# Pigeon.net
KiCad netlist of a schematic drawn in Altium Designer
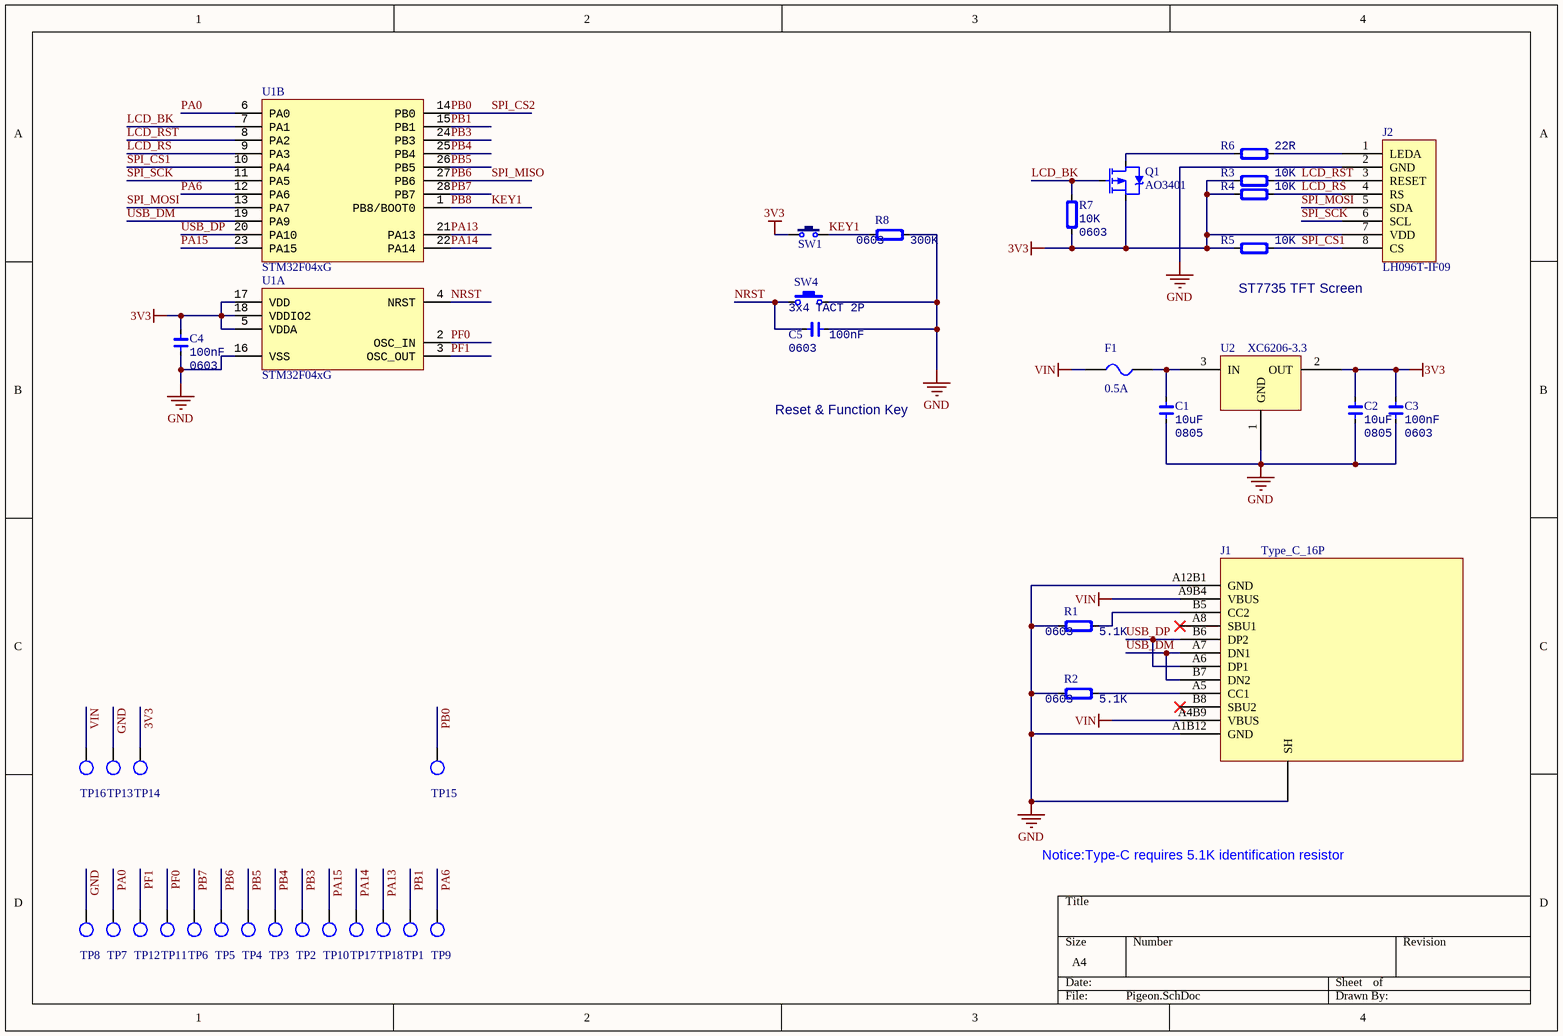
[diagram p0: Pigeon.SchDoc]

(export (version "E")
  (design (tool "Eeschema 10.0.6"))
  (components
    (comp (ref "C1")
      (value "10uF")
      (footprint "PCB_PassiveCap:CAP_0805")
      (description "Capacitor")
      (fields (field (name "TYPE") "0805") (field (name "Comment") "C0805"))
      (libsource (lib "SCH_Passive") (part "Cap_0805"))
    )
    (comp (ref "C2")
      (value "10uF")
      (footprint "PCB_PassiveCap:CAP_0805")
      (description "Capacitor")
      (fields (field (name "TYPE") "0805") (field (name "Comment") "C0805"))
      (libsource (lib "SCH_Passive") (part "Cap_0805"))
    )
    (comp (ref "C3")
      (value "100nF")
      (footprint "PCB_PassiveCap:CAP_0603")
      (description "Capacitor")
      (fields (field (name "TYPE") "0603") (field (name "Comment") "C0603"))
      (libsource (lib "SCH_Passive") (part "Cap_0603"))
    )
    (comp (ref "C4")
      (value "100nF")
      (footprint "PCB_PassiveCap:CAP_0603")
      (description "Capacitor")
      (fields (field (name "TYPE") "0603") (field (name "Comment") "C0603"))
      (libsource (lib "SCH_Passive") (part "Cap_0603"))
    )
    (comp (ref "C5")
      (value "100nF")
      (footprint "PCB_PassiveCap:CAP_0603")
      (description "Capacitor")
      (fields (field (name "TYPE") "0603") (field (name "Comment") "C0603"))
      (libsource (lib "") (part "Cap_0603_1"))
    )
    (comp (ref "F1")
      (value "0.5A")
      (footprint "FU 0805")
      (description "自恢复 0.5A C75464")
      (fields (field (name "版权归属") "源创客"))
      (libsource (lib "10.1 - 保险丝-晶振") (part "FU"))
    )
    (comp (ref "J1")
      (value "Type_C_16P")
      (footprint "Type_C_16P")
      (libsource (lib "LuLib") (part "Type_C_16P"))
    )
    (comp (ref "J2")
      (value "LH096T-IF09")
      (footprint "LH096T-IF09")
      (libsource (lib "LuLib") (part "LH096T-IF09"))
    )
    (comp (ref "Q1") (value "AO3401") (footprint "SOT23-3") (libsource (lib "Schlib1") (part "AO3401")))
    (comp (ref "R1")
      (value "5.1K")
      (footprint "PCB_PassiveRes:RES_0603")
      (description "Resistor 5%")
      (fields (field (name "TYPE") "0603") (field (name "Comment") "R0603"))
      (libsource (lib "SCH_Passive") (part "Res_0603"))
    )
    (comp (ref "R2")
      (value "5.1K")
      (footprint "PCB_PassiveRes:RES_0603")
      (description "Resistor 5%")
      (fields (field (name "TYPE") "0603") (field (name "Comment") "R0603"))
      (libsource (lib "SCH_Passive") (part "Res_0603"))
    )
    (comp (ref "R3")
      (value "10K")
      (footprint "PCB_PassiveRes:RES_0603")
      (description "Resistor")
      (fields (field (name "Comment") "R0603"))
      (libsource (lib "SCH_Passive") (part "Res_0603"))
    )
    (comp (ref "R4")
      (value "10K")
      (footprint "PCB_PassiveRes:RES_0603")
      (description "Resistor")
      (fields (field (name "Comment") "R0603"))
      (libsource (lib "SCH_Passive") (part "Res_0603"))
    )
    (comp (ref "R5")
      (value "10K")
      (footprint "PCB_PassiveRes:RES_0603")
      (description "Resistor")
      (fields (field (name "Comment") "R0603"))
      (libsource (lib "SCH_Passive") (part "Res_0603"))
    )
    (comp (ref "R6")
      (value "22R")
      (footprint "PCB_PassiveRes:RES_0603")
      (description "Resistor")
      (fields (field (name "Comment") "R0603"))
      (libsource (lib "SCH_Passive") (part "Res_0603"))
    )
    (comp (ref "R7")
      (value "10K")
      (footprint "PCB_PassiveRes:RES_0603")
      (description "Resistor")
      (fields (field (name "TYPE") "0603") (field (name "Comment") "R0603"))
      (libsource (lib "SCH_Passive") (part "Res_0603"))
    )
    (comp (ref "R8")
      (value "300K")
      (footprint "PCB_PassiveRes:RES_0603")
      (description "Resistor")
      (fields (field (name "TYPE") "0603") (field (name "Comment") "R0603"))
      (libsource (lib "SCH_Passive") (part "Res_0603"))
    )
    (comp (ref "SW1")
      (value "3x6x5")
      (footprint "TSW 3*6*4.3-S-W")
      (description "3x6轻触开关")
      (fields (field (name "版权归属") "源创客"))
      (libsource (lib "5.1   - 按键-开关") (part "TSW 3x6"))
    )
    (comp (ref "SW4")
      (value "3x4")
      (footprint "PCB_Switch:ButtonTACT_3x4x2_180")
      (description "Button")
      (fields (field (name "TYPE") "TACT 2P") (field (name "Comment") "TACT 2P"))
      (libsource (lib "SCH_Switch") (part "ButtonTACT_3x4x2_180"))
    )
    (comp (ref "TP1")
      (value "TestPin 1.2R 0.3R")
      (footprint "TestPin_1.2R_0.3R")
      (libsource (lib "LuLib") (part "TestPin 1.2R 0.3R"))
    )
    (comp (ref "TP2")
      (value "TestPin 1.2R 0.3R")
      (footprint "TestPin_1.2R_0.3R")
      (libsource (lib "LuLib") (part "TestPin 1.2R 0.3R"))
    )
    (comp (ref "TP3")
      (value "TestPin 1.2R 0.3R")
      (footprint "TestPin_1.2R_0.3R")
      (libsource (lib "LuLib") (part "TestPin 1.2R 0.3R"))
    )
    (comp (ref "TP4")
      (value "TestPin 1.2R 0.3R")
      (footprint "TestPin_1.2R_0.3R")
      (libsource (lib "LuLib") (part "TestPin 1.2R 0.3R"))
    )
    (comp (ref "TP5")
      (value "TestPin 1.2R 0.3R")
      (footprint "TestPin_1.2R_0.3R")
      (libsource (lib "LuLib") (part "TestPin 1.2R 0.3R"))
    )
    (comp (ref "TP6")
      (value "TestPin 1.2R 0.3R")
      (footprint "TestPin_1.2R_0.3R")
      (libsource (lib "LuLib") (part "TestPin 1.2R 0.3R"))
    )
    (comp (ref "TP7")
      (value "TestPin 1.2R 0.3R")
      (footprint "TestPin_1.2R_0.3R")
      (libsource (lib "LuLib") (part "TestPin 1.2R 0.3R"))
    )
    (comp (ref "TP8")
      (value "TestPin 1.2R 0.3R")
      (footprint "TestPin_1.2R_0.3R")
      (libsource (lib "LuLib") (part "TestPin 1.2R 0.3R"))
    )
    (comp (ref "TP9")
      (value "TestPin 1.2R 0.3R")
      (footprint "TestPin_1.2R_0.3R")
      (libsource (lib "LuLib") (part "TestPin 1.2R 0.3R"))
    )
    (comp (ref "TP10")
      (value "TestPin 1.2R 0.3R")
      (footprint "TestPin_1.2R_0.3R")
      (libsource (lib "LuLib") (part "TestPin 1.2R 0.3R"))
    )
    (comp (ref "TP11")
      (value "TestPin 1.2R 0.3R")
      (footprint "TestPin_1.2R_0.3R")
      (libsource (lib "LuLib") (part "TestPin 1.2R 0.3R"))
    )
    (comp (ref "TP12")
      (value "TestPin 1.2R 0.3R")
      (footprint "TestPin_1.2R_0.3R")
      (libsource (lib "LuLib") (part "TestPin 1.2R 0.3R"))
    )
    (comp (ref "TP13")
      (value "TestPin 1.2R 0.3R")
      (footprint "TestPin_1.2R_0.3R")
      (libsource (lib "LuLib") (part "TestPin 1.2R 0.3R"))
    )
    (comp (ref "TP14")
      (value "TestPin 1.2R 0.3R")
      (footprint "TestPin_1.2R_0.3R")
      (libsource (lib "LuLib") (part "TestPin 1.2R 0.3R"))
    )
    (comp (ref "TP15")
      (value "TestPin 1.2R 0.3R")
      (footprint "TestPin_1.2R_0.3R")
      (libsource (lib "LuLib") (part "TestPin 1.2R 0.3R"))
    )
    (comp (ref "TP16")
      (value "TestPin 1.2R 0.3R")
      (footprint "TestPin_1.2R_0.3R")
      (libsource (lib "LuLib") (part "TestPin 1.2R 0.3R"))
    )
    (comp (ref "TP17")
      (value "TestPin 1.2R 0.3R")
      (footprint "TestPin_1.2R_0.3R")
      (libsource (lib "LuLib") (part "TestPin 1.2R 0.3R"))
    )
    (comp (ref "TP18")
      (value "TestPin 1.2R 0.3R")
      (footprint "TestPin_1.2R_0.3R")
      (libsource (lib "LuLib") (part "TestPin 1.2R 0.3R"))
    )
    (comp (ref "U1")
      (value "STM32F04xG")
      (footprint "QFN_P0.5_28_NOPAD")
      (description "MCU")
      (libsource (lib "SCH_IntegratedCircuit") (part "STM32F04xG"))
    )
    (comp (ref "U2") (value "XC6206-3.3") (footprint "SOT23-3") (libsource (lib "LuLib") (part "XC6206-3.3")))
  )
  (nets
    (net (code "1") (name "/KEY1") (class "Default")
      (node (ref "R8") (pin "1") (pinfunction "1_1") (pintype "passive"))
      (node (ref "SW1") (pin "2") (pinfunction "2_2") (pintype "passive"))
      (node (ref "U1") (pin "1") (pinfunction "PB8/BOOT0_1") (pintype "passive"))
    )
    (net (code "2") (name "/LCD_BK") (class "Default")
      (node (ref "Q1") (pin "1") (pinfunction "G_1") (pintype "passive"))
      (node (ref "R7") (pin "2") (pinfunction "2_2") (pintype "passive"))
      (node (ref "U1") (pin "7") (pinfunction "PA1_7") (pintype "passive"))
    )
    (net (code "3") (name "/LCD_RS") (class "Default")
      (node (ref "J2") (pin "4") (pinfunction "RS_4") (pintype "passive"))
      (node (ref "R4") (pin "2") (pinfunction "2_2") (pintype "passive"))
      (node (ref "U1") (pin "9") (pinfunction "PA3_9") (pintype "passive"))
    )
    (net (code "4") (name "/LCD_RST") (class "Default")
      (node (ref "J2") (pin "3") (pinfunction "RESET_3") (pintype "passive"))
      (node (ref "R3") (pin "2") (pinfunction "2_2") (pintype "passive"))
      (node (ref "U1") (pin "8") (pinfunction "PA2_8") (pintype "passive"))
    )
    (net (code "5") (name "/NRST") (class "Default")
      (node (ref "C5") (pin "2") (pinfunction "2_2") (pintype "passive"))
      (node (ref "SW4") (pin "1") (pinfunction "1_1") (pintype "passive"))
      (node (ref "U1") (pin "4") (pinfunction "NRST_4") (pintype "passive"))
    )
    (net (code "6") (name "/PA0") (class "Default")
      (node (ref "TP7") (pin "0") (pinfunction "0_0") (pintype "passive"))
      (node (ref "U1") (pin "6") (pinfunction "PA0_6") (pintype "passive"))
    )
    (net (code "7") (name "/PA6") (class "Default")
      (node (ref "TP9") (pin "0") (pinfunction "0_0") (pintype "passive"))
      (node (ref "U1") (pin "12") (pinfunction "PA6_12") (pintype "passive"))
    )
    (net (code "8") (name "/PA13") (class "Default")
      (node (ref "TP18") (pin "0") (pinfunction "0_0") (pintype "passive"))
      (node (ref "U1") (pin "21") (pinfunction "PA13_21") (pintype "passive"))
    )
    (net (code "9") (name "/PA14") (class "Default")
      (node (ref "TP17") (pin "0") (pinfunction "0_0") (pintype "passive"))
      (node (ref "U1") (pin "22") (pinfunction "PA14_22") (pintype "passive"))
    )
    (net (code "10") (name "/PA15") (class "Default")
      (node (ref "TP10") (pin "0") (pinfunction "0_0") (pintype "passive"))
      (node (ref "U1") (pin "23") (pinfunction "PA15_23") (pintype "passive"))
    )
    (net (code "11") (name "/PB0") (class "Default")
      (node (ref "TP15") (pin "0") (pinfunction "0_0") (pintype "passive"))
      (node (ref "U1") (pin "14") (pinfunction "PB0_14") (pintype "passive"))
    )
    (net (code "12") (name "/PB1") (class "Default")
      (node (ref "TP1") (pin "0") (pinfunction "0_0") (pintype "passive"))
      (node (ref "U1") (pin "15") (pinfunction "PB1_15") (pintype "passive"))
    )
    (net (code "13") (name "/PB3") (class "Default")
      (node (ref "TP2") (pin "0") (pinfunction "0_0") (pintype "passive"))
      (node (ref "U1") (pin "24") (pinfunction "PB3_24") (pintype "passive"))
    )
    (net (code "14") (name "/PB4") (class "Default")
      (node (ref "TP3") (pin "0") (pinfunction "0_0") (pintype "passive"))
      (node (ref "U1") (pin "25") (pinfunction "PB4_25") (pintype "passive"))
    )
    (net (code "15") (name "/PB5") (class "Default")
      (node (ref "TP4") (pin "0") (pinfunction "0_0") (pintype "passive"))
      (node (ref "U1") (pin "26") (pinfunction "PB5_26") (pintype "passive"))
    )
    (net (code "16") (name "/PB6") (class "Default")
      (node (ref "TP5") (pin "0") (pinfunction "0_0") (pintype "passive"))
      (node (ref "U1") (pin "27") (pinfunction "PB6_27") (pintype "passive"))
    )
    (net (code "17") (name "/PB7") (class "Default")
      (node (ref "TP6") (pin "0") (pinfunction "0_0") (pintype "passive"))
      (node (ref "U1") (pin "28") (pinfunction "PB7_28") (pintype "passive"))
    )
    (net (code "18") (name "/PF0") (class "Default")
      (node (ref "TP11") (pin "0") (pinfunction "0_0") (pintype "passive"))
      (node (ref "U1") (pin "2") (pinfunction "OSC_IN_2") (pintype "passive"))
    )
    (net (code "19") (name "/PF1") (class "Default")
      (node (ref "TP12") (pin "0") (pinfunction "0_0") (pintype "passive"))
      (node (ref "U1") (pin "3") (pinfunction "OSC_OUT_3") (pintype "passive"))
    )
    (net (code "20") (name "/SPI_CS1") (class "Default")
      (node (ref "J2") (pin "8") (pinfunction "CS_8") (pintype "passive"))
      (node (ref "R5") (pin "2") (pinfunction "2_2") (pintype "passive"))
      (node (ref "U1") (pin "10") (pinfunction "PA4_10") (pintype "passive"))
    )
    (net (code "21") (name "/SPI_MOSI") (class "Default")
      (node (ref "J2") (pin "5") (pinfunction "SDA_5") (pintype "passive"))
      (node (ref "U1") (pin "13") (pinfunction "PA7_13") (pintype "passive"))
    )
    (net (code "22") (name "/SPI_SCK") (class "Default")
      (node (ref "J2") (pin "6") (pinfunction "SCL_6") (pintype "passive"))
      (node (ref "U1") (pin "11") (pinfunction "PA5_11") (pintype "passive"))
    )
    (net (code "23") (name "/USB_DM") (class "Default")
      (node (ref "J1") (pin "A7") (pinfunction "DN1_A7") (pintype "passive"))
      (node (ref "J1") (pin "B7") (pinfunction "DN2_B7") (pintype "passive"))
      (node (ref "U1") (pin "19") (pinfunction "PA9_19") (pintype "passive"))
    )
    (net (code "24") (name "/USB_DP") (class "Default")
      (node (ref "J1") (pin "A6") (pinfunction "DP1_A6") (pintype "passive"))
      (node (ref "J1") (pin "B6") (pinfunction "DP2_B6") (pintype "passive"))
      (node (ref "U1") (pin "20") (pinfunction "PA10_20") (pintype "passive"))
    )
    (net (code "25") (name "3V3") (class "Default")
      (node (ref "C2") (pin "2") (pinfunction "2_2") (pintype "passive"))
      (node (ref "C3") (pin "2") (pinfunction "2_2") (pintype "passive"))
      (node (ref "C4") (pin "2") (pinfunction "2_2") (pintype "passive"))
      (node (ref "J2") (pin "7") (pinfunction "VDD_7") (pintype "passive"))
      (node (ref "Q1") (pin "2") (pinfunction "S_2") (pintype "passive"))
      (node (ref "R3") (pin "1") (pinfunction "1_1") (pintype "passive"))
      (node (ref "R4") (pin "1") (pinfunction "1_1") (pintype "passive"))
      (node (ref "R5") (pin "1") (pinfunction "1_1") (pintype "passive"))
      (node (ref "R7") (pin "1") (pinfunction "1_1") (pintype "passive"))
      (node (ref "SW1") (pin "1") (pinfunction "1_1") (pintype "passive"))
      (node (ref "TP14") (pin "0") (pinfunction "0_0") (pintype "passive"))
      (node (ref "U1") (pin "17") (pinfunction "VDD_17") (pintype "passive"))
      (node (ref "U1") (pin "18") (pinfunction "VDDIO2_18") (pintype "passive"))
      (node (ref "U1") (pin "5") (pinfunction "VDDA_5") (pintype "passive"))
      (node (ref "U2") (pin "2") (pinfunction "OUT_2") (pintype "passive"))
    )
    (net (code "26") (name "GND") (class "Default")
      (node (ref "C1") (pin "1") (pinfunction "1_1") (pintype "passive"))
      (node (ref "C2") (pin "1") (pinfunction "1_1") (pintype "passive"))
      (node (ref "C3") (pin "1") (pinfunction "1_1") (pintype "passive"))
      (node (ref "C4") (pin "1") (pinfunction "1_1") (pintype "passive"))
      (node (ref "C5") (pin "1") (pinfunction "1_1") (pintype "passive"))
      (node (ref "J1") (pin "0") (pinfunction "SH_0") (pintype "passive"))
      (node (ref "J1") (pin "A12B1") (pinfunction "GND_A12B1") (pintype "passive"))
      (node (ref "J1") (pin "A1B12") (pinfunction "GND_A1B12") (pintype "passive"))
      (node (ref "J2") (pin "2") (pinfunction "GND_2") (pintype "passive"))
      (node (ref "R1") (pin "1") (pinfunction "1_1") (pintype "passive"))
      (node (ref "R2") (pin "1") (pinfunction "1_1") (pintype "passive"))
      (node (ref "R8") (pin "2") (pinfunction "2_2") (pintype "passive"))
      (node (ref "SW4") (pin "2") (pinfunction "2_2") (pintype "passive"))
      (node (ref "TP13") (pin "0") (pinfunction "0_0") (pintype "passive"))
      (node (ref "TP8") (pin "0") (pinfunction "0_0") (pintype "passive"))
      (node (ref "U1") (pin "16") (pinfunction "VSS_16") (pintype "passive"))
      (node (ref "U2") (pin "1") (pinfunction "GND_1") (pintype "passive"))
    )
    (net (code "27") (name "Net-(J1-CC1)") (class "Default")
      (node (ref "J1") (pin "A5") (pinfunction "CC1_A5") (pintype "passive"))
      (node (ref "R2") (pin "2") (pinfunction "2_2") (pintype "passive"))
    )
    (net (code "28") (name "Net-(J1-CC2)") (class "Default")
      (node (ref "J1") (pin "B5") (pinfunction "CC2_B5") (pintype "passive"))
      (node (ref "R1") (pin "2") (pinfunction "2_2") (pintype "passive"))
    )
    (net (code "29") (name "Net-(J2-LEDA)") (class "Default")
      (node (ref "J2") (pin "1") (pinfunction "LEDA_1") (pintype "passive"))
      (node (ref "R6") (pin "1") (pinfunction "1_1") (pintype "passive"))
    )
    (net (code "30") (name "Net-(Q1-D)") (class "Default")
      (node (ref "Q1") (pin "3") (pinfunction "D_3") (pintype "passive"))
      (node (ref "R6") (pin "2") (pinfunction "2_2") (pintype "passive"))
    )
    (net (code "31") (name "Net-(U2-IN)") (class "Default")
      (node (ref "C1") (pin "2") (pinfunction "2_2") (pintype "passive"))
      (node (ref "F1") (pin "2") (pinfunction "2_2") (pintype "passive"))
      (node (ref "U2") (pin "3") (pinfunction "IN_3") (pintype "passive"))
    )
    (net (code "32") (name "VIN") (class "Default")
      (node (ref "F1") (pin "1") (pinfunction "1_1") (pintype "passive"))
      (node (ref "J1") (pin "A4B9") (pinfunction "VBUS_A4B9") (pintype "passive"))
      (node (ref "J1") (pin "A9B4") (pinfunction "VBUS_A9B4") (pintype "passive"))
      (node (ref "TP16") (pin "0") (pinfunction "0_0") (pintype "passive"))
    )
    (net (code "33") (name "unconnected-(J1-SBU1-PadA8)") (class "Default")
      (node (ref "J1") (pin "A8") (pinfunction "SBU1_A8") (pintype "passive+no_connect"))
    )
    (net (code "34") (name "unconnected-(J1-SBU2-PadB8)") (class "Default")
      (node (ref "J1") (pin "B8") (pinfunction "SBU2_B8") (pintype "passive+no_connect"))
    )
  )
)
